# Analog_Signal_Conditioning.net
KiCad netlist of a schematic drawn in Altium Designer
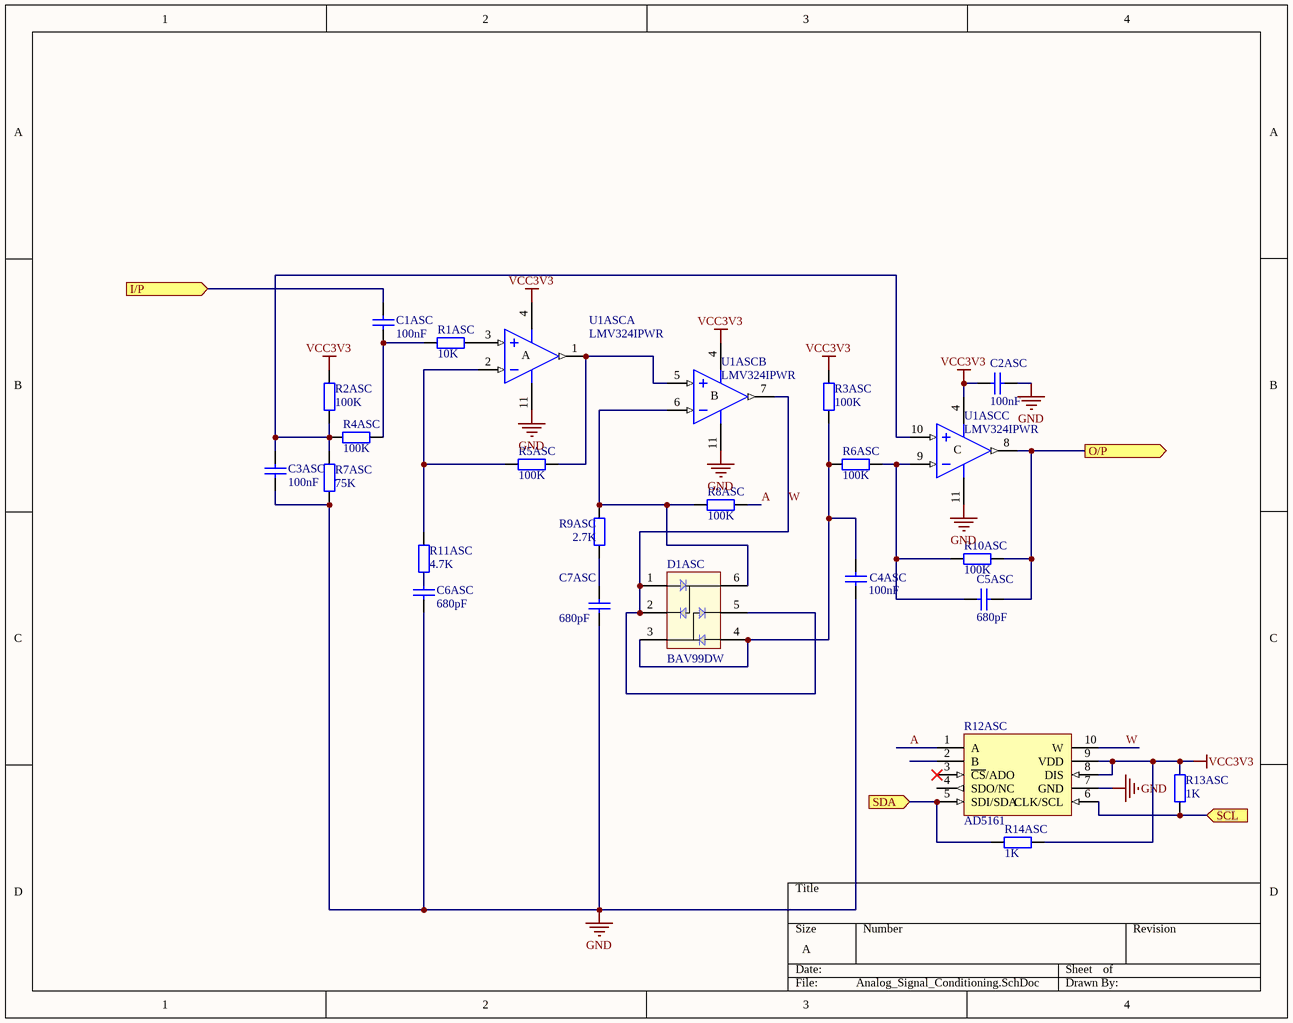
[diagram p0: Analog_Signal_Conditioning.SchDoc]

(export (version "E")
  (design (tool "Eeschema 10.0.6"))
  (components
    (comp (ref "C1ASC")
      (value "100nF")
      (footprint "CC1608-0603")
      (description "Capacitor")
      (fields (field (name "Comment") "Cap"))
      (libsource (lib "Comp") (part "Cap"))
    )
    (comp (ref "C2ASC")
      (value "100nF")
      (footprint "CC1608-0603")
      (description "Capacitor")
      (fields (field (name "Comment") "Cap"))
      (libsource (lib "Comp") (part "Cap"))
    )
    (comp (ref "C3ASC")
      (value "100nF")
      (footprint "CC1608-0603")
      (description "Capacitor")
      (fields (field (name "Comment") "Cap"))
      (libsource (lib "Comp") (part "Cap"))
    )
    (comp (ref "C4ASC")
      (value "100nF")
      (footprint "CC1608-0603")
      (description "Capacitor")
      (fields (field (name "Comment") "Cap"))
      (libsource (lib "Comp") (part "Cap"))
    )
    (comp (ref "C5ASC")
      (value "680pF")
      (footprint "CC1608-0603")
      (description "Capacitor")
      (fields (field (name "Comment") "Cap"))
      (libsource (lib "Comp") (part "Cap"))
    )
    (comp (ref "C6ASC")
      (value "680pF")
      (footprint "CC1608-0603")
      (description "Capacitor")
      (fields (field (name "Comment") "Cap"))
      (libsource (lib "Comp") (part "Cap"))
    )
    (comp (ref "C7ASC")
      (value "680pF")
      (footprint "CC1608-0603")
      (description "Capacitor")
      (fields (field (name "Comment") "Cap"))
      (libsource (lib "Comp") (part "Cap"))
    )
    (comp (ref "D1ASC")
      (value "BAV99DW-7-F")
      (footprint "SOT-323-6L")
      (description "Quad surface mount switching diode array")
      (fields (field (name "MANUFACTURER") "Diodes Incorporated"))
      (libsource (lib "Comp") (part "BAV99DW"))
    )
    (comp (ref "R1ASC")
      (value "10K")
      (footprint "CR1608-0603")
      (description "Resistor")
      (fields (field (name "Comment") "Res"))
      (libsource (lib "") (part "Res_1"))
    )
    (comp (ref "R2ASC")
      (value "100K")
      (footprint "CR1608-0603")
      (description "Resistor")
      (fields (field (name "Comment") "Res"))
      (libsource (lib "Comp") (part "Res"))
    )
    (comp (ref "R3ASC")
      (value "100K")
      (footprint "CR1608-0603")
      (description "Resistor")
      (fields (field (name "Comment") "Res"))
      (libsource (lib "Comp") (part "Res"))
    )
    (comp (ref "R4ASC")
      (value "100K")
      (footprint "CR1608-0603")
      (description "Resistor")
      (fields (field (name "Comment") "Res"))
      (libsource (lib "") (part "Res_1"))
    )
    (comp (ref "R5ASC")
      (value "100K")
      (footprint "CR1608-0603")
      (description "Resistor")
      (fields (field (name "Comment") "Res"))
      (libsource (lib "") (part "Res_1"))
    )
    (comp (ref "R6ASC")
      (value "100K")
      (footprint "CR1608-0603")
      (description "Resistor")
      (fields (field (name "Comment") "Res"))
      (libsource (lib "") (part "Res_1"))
    )
    (comp (ref "R7ASC")
      (value "75K")
      (footprint "CR1608-0603")
      (description "Resistor")
      (fields (field (name "Comment") "Res"))
      (libsource (lib "Comp") (part "Res"))
    )
    (comp (ref "R8ASC")
      (value "100K")
      (footprint "CR1608-0603")
      (description "Resistor")
      (fields (field (name "Comment") "Res"))
      (libsource (lib "") (part "Res_2"))
    )
    (comp (ref "R9ASC")
      (value "2.7K")
      (footprint "CR1608-0603")
      (description "Resistor")
      (fields (field (name "Comment") "Res"))
      (libsource (lib "Comp") (part "Res"))
    )
    (comp (ref "R10ASC")
      (value "100K")
      (footprint "CR1608-0603")
      (description "Resistor")
      (fields (field (name "Comment") "Res"))
      (libsource (lib "") (part "Res_1"))
    )
    (comp (ref "R11ASC")
      (value "4.7K")
      (footprint "CR1608-0603")
      (description "Resistor")
      (fields (field (name "Comment") "Res"))
      (libsource (lib "") (part "Res_3"))
    )
    (comp (ref "R12ASC")
      (value "AD5161")
      (footprint "TSSO3x5-G10")
      (description "AD5161 SPI/I2C Selectable Digital Potentiometer")
      (fields (field (name "MANUFACTURER") "Analog Devices"))
      (libsource (lib "*") (part "AD5161_3x5"))
    )
    (comp (ref "R13ASC")
      (value "1K")
      (footprint "CR1608-0603")
      (description "Resistor")
      (fields (field (name "Comment") "Res"))
      (libsource (lib "") (part "Res_1"))
    )
    (comp (ref "R14ASC")
      (value "1K")
      (footprint "CR1608-0603")
      (description "Resistor")
      (fields (field (name "Comment") "Res"))
      (libsource (lib "*") (part "Res"))
    )
    (comp (ref "U1ASC")
      (value "LMV324IPWR")
      (footprint "TSSO5x6-G14/X.3")
      (description "Rail-to-Rail Operational Amplifier")
      (fields (field (name "MANUFACTURER") "Texas Instruments"))
      (libsource (lib "Comp") (part "LMV324IPWR"))
    )
  )
  (nets
    (net (code "1") (name "/A") (class "Default")
      (node (ref "R12ASC") (pin "1") (pinfunction "A_1") (pintype "passive"))
      (node (ref "R8ASC") (pin "2") (pinfunction "2_2") (pintype "passive"))
    )
    (net (code "2") (name "/I{slash}P") (class "Default")
      (node (ref "C1ASC") (pin "2") (pinfunction "2_2") (pintype "passive"))
    )
    (net (code "3") (name "/O{slash}P") (class "Default")
      (node (ref "C5ASC") (pin "1") (pinfunction "1_1") (pintype "passive"))
      (node (ref "R10ASC") (pin "1") (pinfunction "1_1") (pintype "passive"))
      (node (ref "U1ASC") (pin "8") (pinfunction "OUT_8") (pintype "output"))
    )
    (net (code "4") (name "/SCL") (class "Default")
      (node (ref "R12ASC") (pin "6") (pinfunction "CLK/SCL_6") (pintype "input"))
      (node (ref "R13ASC") (pin "1") (pinfunction "1_1") (pintype "passive"))
    )
    (net (code "5") (name "/SDA") (class "Default")
      (node (ref "R12ASC") (pin "5") (pinfunction "SDI/SDA_5") (pintype "input"))
      (node (ref "R14ASC") (pin "2") (pinfunction "2_2") (pintype "passive"))
    )
    (net (code "6") (name "/W") (class "Default")
      (node (ref "D1ASC") (pin "1") (pinfunction "A1_1") (pintype "passive"))
      (node (ref "D1ASC") (pin "2") (pinfunction "C1_2") (pintype "passive"))
      (node (ref "D1ASC") (pin "5") (pinfunction "C2_5") (pintype "passive"))
      (node (ref "R12ASC") (pin "10") (pinfunction "W_10") (pintype "passive"))
      (node (ref "U1ASC") (pin "7") (pinfunction "OUT_7") (pintype "output"))
    )
    (net (code "7") (name "GND") (class "Default")
      (node (ref "C2ASC") (pin "1") (pinfunction "1_1") (pintype "passive"))
      (node (ref "C3ASC") (pin "1") (pinfunction "1_1") (pintype "passive"))
      (node (ref "C4ASC") (pin "1") (pinfunction "1_1") (pintype "passive"))
      (node (ref "C6ASC") (pin "1") (pinfunction "1_1") (pintype "passive"))
      (node (ref "C7ASC") (pin "1") (pinfunction "1_1") (pintype "passive"))
      (node (ref "R12ASC") (pin "7") (pinfunction "GND_7") (pintype "power_in"))
      (node (ref "R7ASC") (pin "1") (pinfunction "1_1") (pintype "passive"))
      (node (ref "U1ASC") (pin "11") (pinfunction "V-_11") (pintype "power_in"))
    )
    (net (code "8") (name "Net-(C1ASC-Pad1)") (class "Default")
      (node (ref "C1ASC") (pin "1") (pinfunction "1_1") (pintype "passive"))
      (node (ref "R1ASC") (pin "2") (pinfunction "2_2") (pintype "passive"))
      (node (ref "R4ASC") (pin "1") (pinfunction "1_1") (pintype "passive"))
    )
    (net (code "9") (name "Net-(C6ASC-Pad2)") (class "Default")
      (node (ref "C6ASC") (pin "2") (pinfunction "2_2") (pintype "passive"))
      (node (ref "R11ASC") (pin "2") (pinfunction "2_2") (pintype "passive"))
    )
    (net (code "10") (name "Net-(C7ASC-Pad2)") (class "Default")
      (node (ref "C7ASC") (pin "2") (pinfunction "2_2") (pintype "passive"))
      (node (ref "R9ASC") (pin "1") (pinfunction "1_1") (pintype "passive"))
    )
    (net (code "11") (name "Net-(D1ASC-A2)") (class "Default")
      (node (ref "C4ASC") (pin "2") (pinfunction "2_2") (pintype "passive"))
      (node (ref "D1ASC") (pin "3") (pinfunction "AC2_3") (pintype "passive"))
      (node (ref "D1ASC") (pin "4") (pinfunction "A2_4") (pintype "passive"))
      (node (ref "R3ASC") (pin "1") (pinfunction "1_1") (pintype "passive"))
      (node (ref "R6ASC") (pin "2") (pinfunction "2_2") (pintype "passive"))
    )
    (net (code "12") (name "Net-(D1ASC-AC1)") (class "Default")
      (node (ref "D1ASC") (pin "6") (pinfunction "AC1_6") (pintype "passive"))
      (node (ref "R8ASC") (pin "1") (pinfunction "1_1") (pintype "passive"))
      (node (ref "R9ASC") (pin "2") (pinfunction "2_2") (pintype "passive"))
      (node (ref "U1ASC") (pin "6") (pinfunction "IN-_6") (pintype "input"))
    )
    (net (code "13") (name "Net-(U1ASCA-IN+)") (class "Default")
      (node (ref "R1ASC") (pin "1") (pinfunction "1_1") (pintype "passive"))
      (node (ref "U1ASC") (pin "3") (pinfunction "IN+_3") (pintype "input"))
    )
    (net (code "14") (name "Net-(U1ASCA-IN-)") (class "Default")
      (node (ref "R11ASC") (pin "1") (pinfunction "1_1") (pintype "passive"))
      (node (ref "R5ASC") (pin "2") (pinfunction "2_2") (pintype "passive"))
      (node (ref "U1ASC") (pin "2") (pinfunction "IN-_2") (pintype "input"))
    )
    (net (code "15") (name "Net-(U1ASCA-OUT)") (class "Default")
      (node (ref "R5ASC") (pin "1") (pinfunction "1_1") (pintype "passive"))
      (node (ref "U1ASC") (pin "1") (pinfunction "OUT_1") (pintype "output"))
      (node (ref "U1ASC") (pin "5") (pinfunction "IN+_5") (pintype "input"))
    )
    (net (code "16") (name "Net-(U1ASCC-IN+)") (class "Default")
      (node (ref "C3ASC") (pin "2") (pinfunction "2_2") (pintype "passive"))
      (node (ref "R2ASC") (pin "1") (pinfunction "1_1") (pintype "passive"))
      (node (ref "R4ASC") (pin "2") (pinfunction "2_2") (pintype "passive"))
      (node (ref "R7ASC") (pin "2") (pinfunction "2_2") (pintype "passive"))
      (node (ref "U1ASC") (pin "10") (pinfunction "IN+_10") (pintype "input"))
    )
    (net (code "17") (name "Net-(U1ASCC-IN-)") (class "Default")
      (node (ref "C5ASC") (pin "2") (pinfunction "2_2") (pintype "passive"))
      (node (ref "R10ASC") (pin "2") (pinfunction "2_2") (pintype "passive"))
      (node (ref "R6ASC") (pin "1") (pinfunction "1_1") (pintype "passive"))
      (node (ref "U1ASC") (pin "9") (pinfunction "IN-_9") (pintype "input"))
    )
    (net (code "18") (name "VCC3V3") (class "Default")
      (node (ref "C2ASC") (pin "2") (pinfunction "2_2") (pintype "passive"))
      (node (ref "R12ASC") (pin "8") (pinfunction "DIS_8") (pintype "input"))
      (node (ref "R12ASC") (pin "9") (pinfunction "VDD_9") (pintype "power_in"))
      (node (ref "R13ASC") (pin "2") (pinfunction "2_2") (pintype "passive"))
      (node (ref "R14ASC") (pin "1") (pinfunction "1_1") (pintype "passive"))
      (node (ref "R2ASC") (pin "2") (pinfunction "2_2") (pintype "passive"))
      (node (ref "R3ASC") (pin "2") (pinfunction "2_2") (pintype "passive"))
      (node (ref "U1ASC") (pin "4") (pinfunction "V+_4") (pintype "power_in"))
    )
    (net (code "19") (name "unconnected-(R12ASC-B-Pad2)") (class "Default")
      (node (ref "R12ASC") (pin "2") (pinfunction "B_2") (pintype "passive"))
    )
    (net (code "20") (name "unconnected-(R12ASC-SDO{slash}NC-Pad4)") (class "Default")
      (node (ref "R12ASC") (pin "4") (pinfunction "SDO/NC_4") (pintype "output"))
    )
    (net (code "21") (name "unconnected-(R12ASC-~{CS}{slash}ADO-Pad3)") (class "Default")
      (node (ref "R12ASC") (pin "3") (pinfunction "~{CS}/ADO_3") (pintype "input+no_connect"))
    )
  )
)
